# AUX_Stufe.net
KiCad netlist of a schematic drawn in Altium Designer
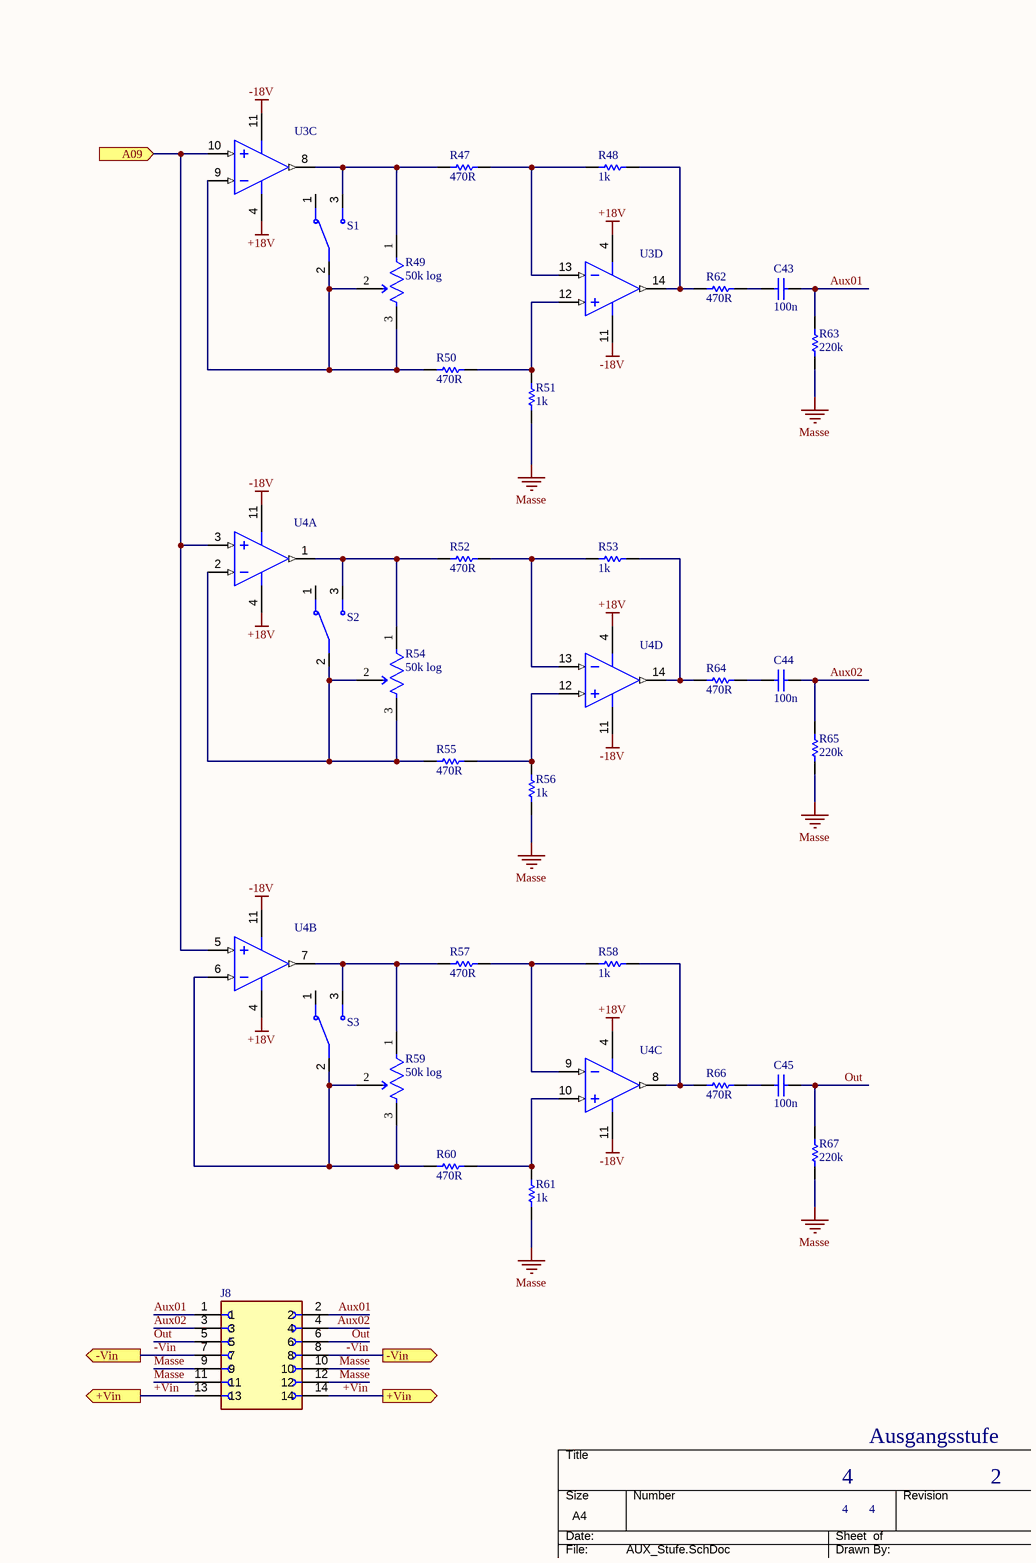
[diagram p0: AUX_Stufe.SchDoc]

(export (version "E")
  (design (tool "Eeschema 10.0.6"))
  (components
    (comp (ref "C43")
      (value "100n")
      (footprint "0805")
      (description "0805 Kondensator")
      (libsource (lib "Bauteile") (part "0805 Kondensator"))
    )
    (comp (ref "C44")
      (value "100n")
      (footprint "0805")
      (description "0805 Kondensator")
      (libsource (lib "Bauteile") (part "0805 Kondensator"))
    )
    (comp (ref "C45")
      (value "100n")
      (footprint "0805")
      (description "0805 Kondensator")
      (libsource (lib "Bauteile") (part "0805 Kondensator"))
    )
    (comp (ref "J8")
      (value "Connector x14")
      (footprint "Connector x14")
      (description "14 Position Header Connector Through Hole")
      (fields (field (name "MF") "Sullins Connector") (field (name "MP") "SFH11-PBPC-D07-ST-BK"))
      (libsource (lib "Bauteile") (part "Connector x14"))
    )
    (comp (ref "R47")
      (value "470R")
      (footprint "0805")
      (description "0805 Widerstand")
      (libsource (lib "Bauteile") (part "0805 Widerstand"))
    )
    (comp (ref "R48")
      (value "1k")
      (footprint "0805")
      (description "0805 Widerstand")
      (libsource (lib "Bauteile") (part "0805 Widerstand"))
    )
    (comp (ref "R49")
      (value "50k log")
      (footprint "Connector x3")
      (description "Potentiometer")
      (libsource (lib "Bauteile") (part "Potentiometer Buchsenleiste"))
    )
    (comp (ref "R50")
      (value "470R")
      (footprint "0805")
      (description "0805 Widerstand")
      (libsource (lib "Bauteile") (part "0805 Widerstand"))
    )
    (comp (ref "R51")
      (value "1k")
      (footprint "0805")
      (description "0805 Widerstand")
      (libsource (lib "Bauteile") (part "0805 Widerstand"))
    )
    (comp (ref "R52")
      (value "470R")
      (footprint "0805")
      (description "0805 Widerstand")
      (libsource (lib "Bauteile") (part "0805 Widerstand"))
    )
    (comp (ref "R53")
      (value "1k")
      (footprint "0805")
      (description "0805 Widerstand")
      (libsource (lib "Bauteile") (part "0805 Widerstand"))
    )
    (comp (ref "R54")
      (value "50k log")
      (footprint "Connector x3")
      (description "Potentiometer")
      (libsource (lib "Bauteile") (part "Potentiometer Buchsenleiste"))
    )
    (comp (ref "R55")
      (value "470R")
      (footprint "0805")
      (description "0805 Widerstand")
      (libsource (lib "Bauteile") (part "0805 Widerstand"))
    )
    (comp (ref "R56")
      (value "1k")
      (footprint "0805")
      (description "0805 Widerstand")
      (libsource (lib "Bauteile") (part "0805 Widerstand"))
    )
    (comp (ref "R57")
      (value "470R")
      (footprint "0805")
      (description "0805 Widerstand")
      (libsource (lib "Bauteile") (part "0805 Widerstand"))
    )
    (comp (ref "R58")
      (value "1k")
      (footprint "0805")
      (description "0805 Widerstand")
      (libsource (lib "Bauteile") (part "0805 Widerstand"))
    )
    (comp (ref "R59")
      (value "50k log")
      (footprint "Connector x3")
      (description "Potentiometer")
      (libsource (lib "Bauteile") (part "Potentiometer Buchsenleiste"))
    )
    (comp (ref "R60")
      (value "470R")
      (footprint "0805")
      (description "0805 Widerstand")
      (libsource (lib "Bauteile") (part "0805 Widerstand"))
    )
    (comp (ref "R61")
      (value "1k")
      (footprint "0805")
      (description "0805 Widerstand")
      (libsource (lib "Bauteile") (part "0805 Widerstand"))
    )
    (comp (ref "R62")
      (value "470R")
      (footprint "0805")
      (description "0805 Widerstand")
      (libsource (lib "Bauteile") (part "0805 Widerstand"))
    )
    (comp (ref "R63")
      (value "220k")
      (footprint "0805")
      (description "0805 Widerstand")
      (libsource (lib "Bauteile") (part "0805 Widerstand"))
    )
    (comp (ref "R64")
      (value "470R")
      (footprint "0805")
      (description "0805 Widerstand")
      (libsource (lib "Bauteile") (part "0805 Widerstand"))
    )
    (comp (ref "R65")
      (value "220k")
      (footprint "0805")
      (description "0805 Widerstand")
      (libsource (lib "Bauteile") (part "0805 Widerstand"))
    )
    (comp (ref "R66")
      (value "470R")
      (footprint "0805")
      (description "0805 Widerstand")
      (libsource (lib "Bauteile") (part "0805 Widerstand"))
    )
    (comp (ref "R67")
      (value "220k")
      (footprint "0805")
      (description "0805 Widerstand")
      (libsource (lib "Bauteile") (part "0805 Widerstand"))
    )
    (comp (ref "S1")
      (value "Schalter Buchsenleiste")
      (footprint "Connector x3")
      (description "Toggle Switch SPDT Through Hole")
      (fields (field (name "MP") "100SP1T1B4M2QE"))
      (libsource (lib "Bauteile") (part "Schalter Buchsenleiste"))
    )
    (comp (ref "S2")
      (value "Schalter Buchsenleiste")
      (footprint "Connector x3")
      (description "Toggle Switch SPDT Through Hole")
      (fields (field (name "MP") "100SP1T1B4M2QE"))
      (libsource (lib "Bauteile") (part "Schalter Buchsenleiste"))
    )
    (comp (ref "S3")
      (value "Schalter Buchsenleiste")
      (footprint "Connector x3")
      (description "Toggle Switch SPDT Through Hole")
      (fields (field (name "MP") "100SP1T1B4M2QE"))
      (libsource (lib "Bauteile") (part "Schalter Buchsenleiste"))
    )
    (comp (ref "U3")
      (value "OPA4134UA")
      (footprint "DIP14 IC Socket")
      (fields (field (name "MANUFACTURER") "Texas Instruments"))
      (libsource (lib "Bauteile") (part "SOIC OPA4134UA"))
    )
    (comp (ref "U4")
      (value "OPA4134UA")
      (footprint "DIP14 IC Socket")
      (fields (field (name "MANUFACTURER") "Texas Instruments"))
      (libsource (lib "Bauteile") (part "SOIC OPA4134UA"))
    )
  )
  (nets
    (net (code "1") (name "+18V") (class "Default")
      (node (ref "U3") (pin "4") (pinfunction "V+_4") (pintype "power_in"))
      (node (ref "U4") (pin "4") (pinfunction "V+_4") (pintype "power_in"))
    )
    (net (code "2") (name "-18V") (class "Default")
      (node (ref "U3") (pin "11") (pinfunction "V-_11") (pintype "power_in"))
      (node (ref "U4") (pin "11") (pinfunction "V-_11") (pintype "power_in"))
    )
    (net (code "3") (name "/+Vin") (class "Default")
      (node (ref "J8") (pin "13") (pinfunction "13_13") (pintype "passive"))
      (node (ref "J8") (pin "14") (pinfunction "14_14") (pintype "passive"))
    )
    (net (code "4") (name "/-Vin") (class "Default")
      (node (ref "J8") (pin "7") (pinfunction "7_7") (pintype "passive"))
      (node (ref "J8") (pin "8") (pinfunction "8_8") (pintype "passive"))
    )
    (net (code "5") (name "/A09") (class "Default")
      (node (ref "U3") (pin "10") (pinfunction "IN_C+_10") (pintype "input"))
      (node (ref "U4") (pin "3") (pinfunction "IN_A+_3") (pintype "input"))
      (node (ref "U4") (pin "5") (pinfunction "IN_B+_5") (pintype "input"))
    )
    (net (code "6") (name "/Aux01") (class "Default")
      (node (ref "C43") (pin "2") (pinfunction "2_2") (pintype "passive"))
      (node (ref "J8") (pin "1") (pinfunction "1_1") (pintype "passive"))
      (node (ref "J8") (pin "2") (pinfunction "2_2") (pintype "passive"))
      (node (ref "R63") (pin "2") (pinfunction "2_2") (pintype "passive"))
    )
    (net (code "7") (name "/Aux02") (class "Default")
      (node (ref "C44") (pin "2") (pinfunction "2_2") (pintype "passive"))
      (node (ref "J8") (pin "3") (pinfunction "3_3") (pintype "passive"))
      (node (ref "J8") (pin "4") (pinfunction "4_4") (pintype "passive"))
      (node (ref "R65") (pin "2") (pinfunction "2_2") (pintype "passive"))
    )
    (net (code "8") (name "/Out") (class "Default")
      (node (ref "C45") (pin "2") (pinfunction "2_2") (pintype "passive"))
      (node (ref "J8") (pin "5") (pinfunction "5_5") (pintype "passive"))
      (node (ref "J8") (pin "6") (pinfunction "6_6") (pintype "passive"))
      (node (ref "R67") (pin "2") (pinfunction "2_2") (pintype "passive"))
    )
    (net (code "9") (name "Masse") (class "Default")
      (node (ref "J8") (pin "10") (pinfunction "10_10") (pintype "passive"))
      (node (ref "J8") (pin "11") (pinfunction "11_11") (pintype "passive"))
      (node (ref "J8") (pin "12") (pinfunction "12_12") (pintype "passive"))
      (node (ref "J8") (pin "9") (pinfunction "9_9") (pintype "passive"))
      (node (ref "R51") (pin "1") (pinfunction "1_1") (pintype "passive"))
      (node (ref "R56") (pin "1") (pinfunction "1_1") (pintype "passive"))
      (node (ref "R61") (pin "1") (pinfunction "1_1") (pintype "passive"))
      (node (ref "R63") (pin "1") (pinfunction "1_1") (pintype "passive"))
      (node (ref "R65") (pin "1") (pinfunction "1_1") (pintype "passive"))
      (node (ref "R67") (pin "1") (pinfunction "1_1") (pintype "passive"))
    )
    (net (code "10") (name "Net-(C43-Pad1)") (class "Default")
      (node (ref "C43") (pin "1") (pinfunction "1_1") (pintype "passive"))
      (node (ref "R62") (pin "2") (pinfunction "2_2") (pintype "passive"))
    )
    (net (code "11") (name "Net-(C44-Pad1)") (class "Default")
      (node (ref "C44") (pin "1") (pinfunction "1_1") (pintype "passive"))
      (node (ref "R64") (pin "2") (pinfunction "2_2") (pintype "passive"))
    )
    (net (code "12") (name "Net-(C45-Pad1)") (class "Default")
      (node (ref "C45") (pin "1") (pinfunction "1_1") (pintype "passive"))
      (node (ref "R66") (pin "2") (pinfunction "2_2") (pintype "passive"))
    )
    (net (code "13") (name "Net-(R49-a)") (class "Default")
      (node (ref "R47") (pin "1") (pinfunction "1_1") (pintype "passive"))
      (node (ref "R49") (pin "1") (pinfunction "a_1") (pintype "passive"))
      (node (ref "S1") (pin "3") (pinfunction "3_3") (pintype "passive"))
      (node (ref "U3") (pin "8") (pinfunction "OUT_C_8") (pintype "output"))
    )
    (net (code "14") (name "Net-(R49-b)") (class "Default")
      (node (ref "R49") (pin "2") (pinfunction "b_2") (pintype "passive"))
      (node (ref "R49") (pin "3") (pinfunction "c_3") (pintype "passive"))
      (node (ref "R50") (pin "1") (pinfunction "1_1") (pintype "passive"))
      (node (ref "S1") (pin "2") (pinfunction "2_2") (pintype "passive"))
      (node (ref "U3") (pin "9") (pinfunction "IN_C-_9") (pintype "input"))
    )
    (net (code "15") (name "Net-(R54-a)") (class "Default")
      (node (ref "R52") (pin "1") (pinfunction "1_1") (pintype "passive"))
      (node (ref "R54") (pin "1") (pinfunction "a_1") (pintype "passive"))
      (node (ref "S2") (pin "3") (pinfunction "3_3") (pintype "passive"))
      (node (ref "U4") (pin "1") (pinfunction "OUT_A_1") (pintype "output"))
    )
    (net (code "16") (name "Net-(R54-b)") (class "Default")
      (node (ref "R54") (pin "2") (pinfunction "b_2") (pintype "passive"))
      (node (ref "R54") (pin "3") (pinfunction "c_3") (pintype "passive"))
      (node (ref "R55") (pin "1") (pinfunction "1_1") (pintype "passive"))
      (node (ref "S2") (pin "2") (pinfunction "2_2") (pintype "passive"))
      (node (ref "U4") (pin "2") (pinfunction "IN_A-_2") (pintype "input"))
    )
    (net (code "17") (name "Net-(R59-a)") (class "Default")
      (node (ref "R57") (pin "1") (pinfunction "1_1") (pintype "passive"))
      (node (ref "R59") (pin "1") (pinfunction "a_1") (pintype "passive"))
      (node (ref "S3") (pin "3") (pinfunction "3_3") (pintype "passive"))
      (node (ref "U4") (pin "7") (pinfunction "OUT_B_7") (pintype "output"))
    )
    (net (code "18") (name "Net-(R59-b)") (class "Default")
      (node (ref "R59") (pin "2") (pinfunction "b_2") (pintype "passive"))
      (node (ref "R59") (pin "3") (pinfunction "c_3") (pintype "passive"))
      (node (ref "R60") (pin "1") (pinfunction "1_1") (pintype "passive"))
      (node (ref "S3") (pin "2") (pinfunction "2_2") (pintype "passive"))
      (node (ref "U4") (pin "6") (pinfunction "IN_B-_6") (pintype "input"))
    )
    (net (code "19") (name "Net-(U3D-IN_D+)") (class "Default")
      (node (ref "R50") (pin "2") (pinfunction "2_2") (pintype "passive"))
      (node (ref "R51") (pin "2") (pinfunction "2_2") (pintype "passive"))
      (node (ref "U3") (pin "12") (pinfunction "IN_D+_12") (pintype "input"))
    )
    (net (code "20") (name "Net-(U3D-IN_D-)") (class "Default")
      (node (ref "R47") (pin "2") (pinfunction "2_2") (pintype "passive"))
      (node (ref "R48") (pin "1") (pinfunction "1_1") (pintype "passive"))
      (node (ref "U3") (pin "13") (pinfunction "IN_D-_13") (pintype "input"))
    )
    (net (code "21") (name "Net-(U3D-OUT_D)") (class "Default")
      (node (ref "R48") (pin "2") (pinfunction "2_2") (pintype "passive"))
      (node (ref "R62") (pin "1") (pinfunction "1_1") (pintype "passive"))
      (node (ref "U3") (pin "14") (pinfunction "OUT_D_14") (pintype "output"))
    )
    (net (code "22") (name "Net-(U4C-IN_C+)") (class "Default")
      (node (ref "R60") (pin "2") (pinfunction "2_2") (pintype "passive"))
      (node (ref "R61") (pin "2") (pinfunction "2_2") (pintype "passive"))
      (node (ref "U4") (pin "10") (pinfunction "IN_C+_10") (pintype "input"))
    )
    (net (code "23") (name "Net-(U4C-IN_C-)") (class "Default")
      (node (ref "R57") (pin "2") (pinfunction "2_2") (pintype "passive"))
      (node (ref "R58") (pin "1") (pinfunction "1_1") (pintype "passive"))
      (node (ref "U4") (pin "9") (pinfunction "IN_C-_9") (pintype "input"))
    )
    (net (code "24") (name "Net-(U4C-OUT_C)") (class "Default")
      (node (ref "R58") (pin "2") (pinfunction "2_2") (pintype "passive"))
      (node (ref "R66") (pin "1") (pinfunction "1_1") (pintype "passive"))
      (node (ref "U4") (pin "8") (pinfunction "OUT_C_8") (pintype "output"))
    )
    (net (code "25") (name "Net-(U4D-IN_D+)") (class "Default")
      (node (ref "R55") (pin "2") (pinfunction "2_2") (pintype "passive"))
      (node (ref "R56") (pin "2") (pinfunction "2_2") (pintype "passive"))
      (node (ref "U4") (pin "12") (pinfunction "IN_D+_12") (pintype "input"))
    )
    (net (code "26") (name "Net-(U4D-IN_D-)") (class "Default")
      (node (ref "R52") (pin "2") (pinfunction "2_2") (pintype "passive"))
      (node (ref "R53") (pin "1") (pinfunction "1_1") (pintype "passive"))
      (node (ref "U4") (pin "13") (pinfunction "IN_D-_13") (pintype "input"))
    )
    (net (code "27") (name "Net-(U4D-OUT_D)") (class "Default")
      (node (ref "R53") (pin "2") (pinfunction "2_2") (pintype "passive"))
      (node (ref "R64") (pin "1") (pinfunction "1_1") (pintype "passive"))
      (node (ref "U4") (pin "14") (pinfunction "OUT_D_14") (pintype "output"))
    )
    (net (code "28") (name "unconnected-(S1-Pad1)") (class "Default")
      (node (ref "S1") (pin "1") (pinfunction "1_1") (pintype "passive"))
    )
    (net (code "29") (name "unconnected-(S2-Pad1)") (class "Default")
      (node (ref "S2") (pin "1") (pinfunction "1_1") (pintype "passive"))
    )
    (net (code "30") (name "unconnected-(S3-Pad1)") (class "Default")
      (node (ref "S3") (pin "1") (pinfunction "1_1") (pintype "passive"))
    )
  )
)
